# Kitchenkopf-v1_1.net
KiCad netlist of a schematic drawn in EAGLE
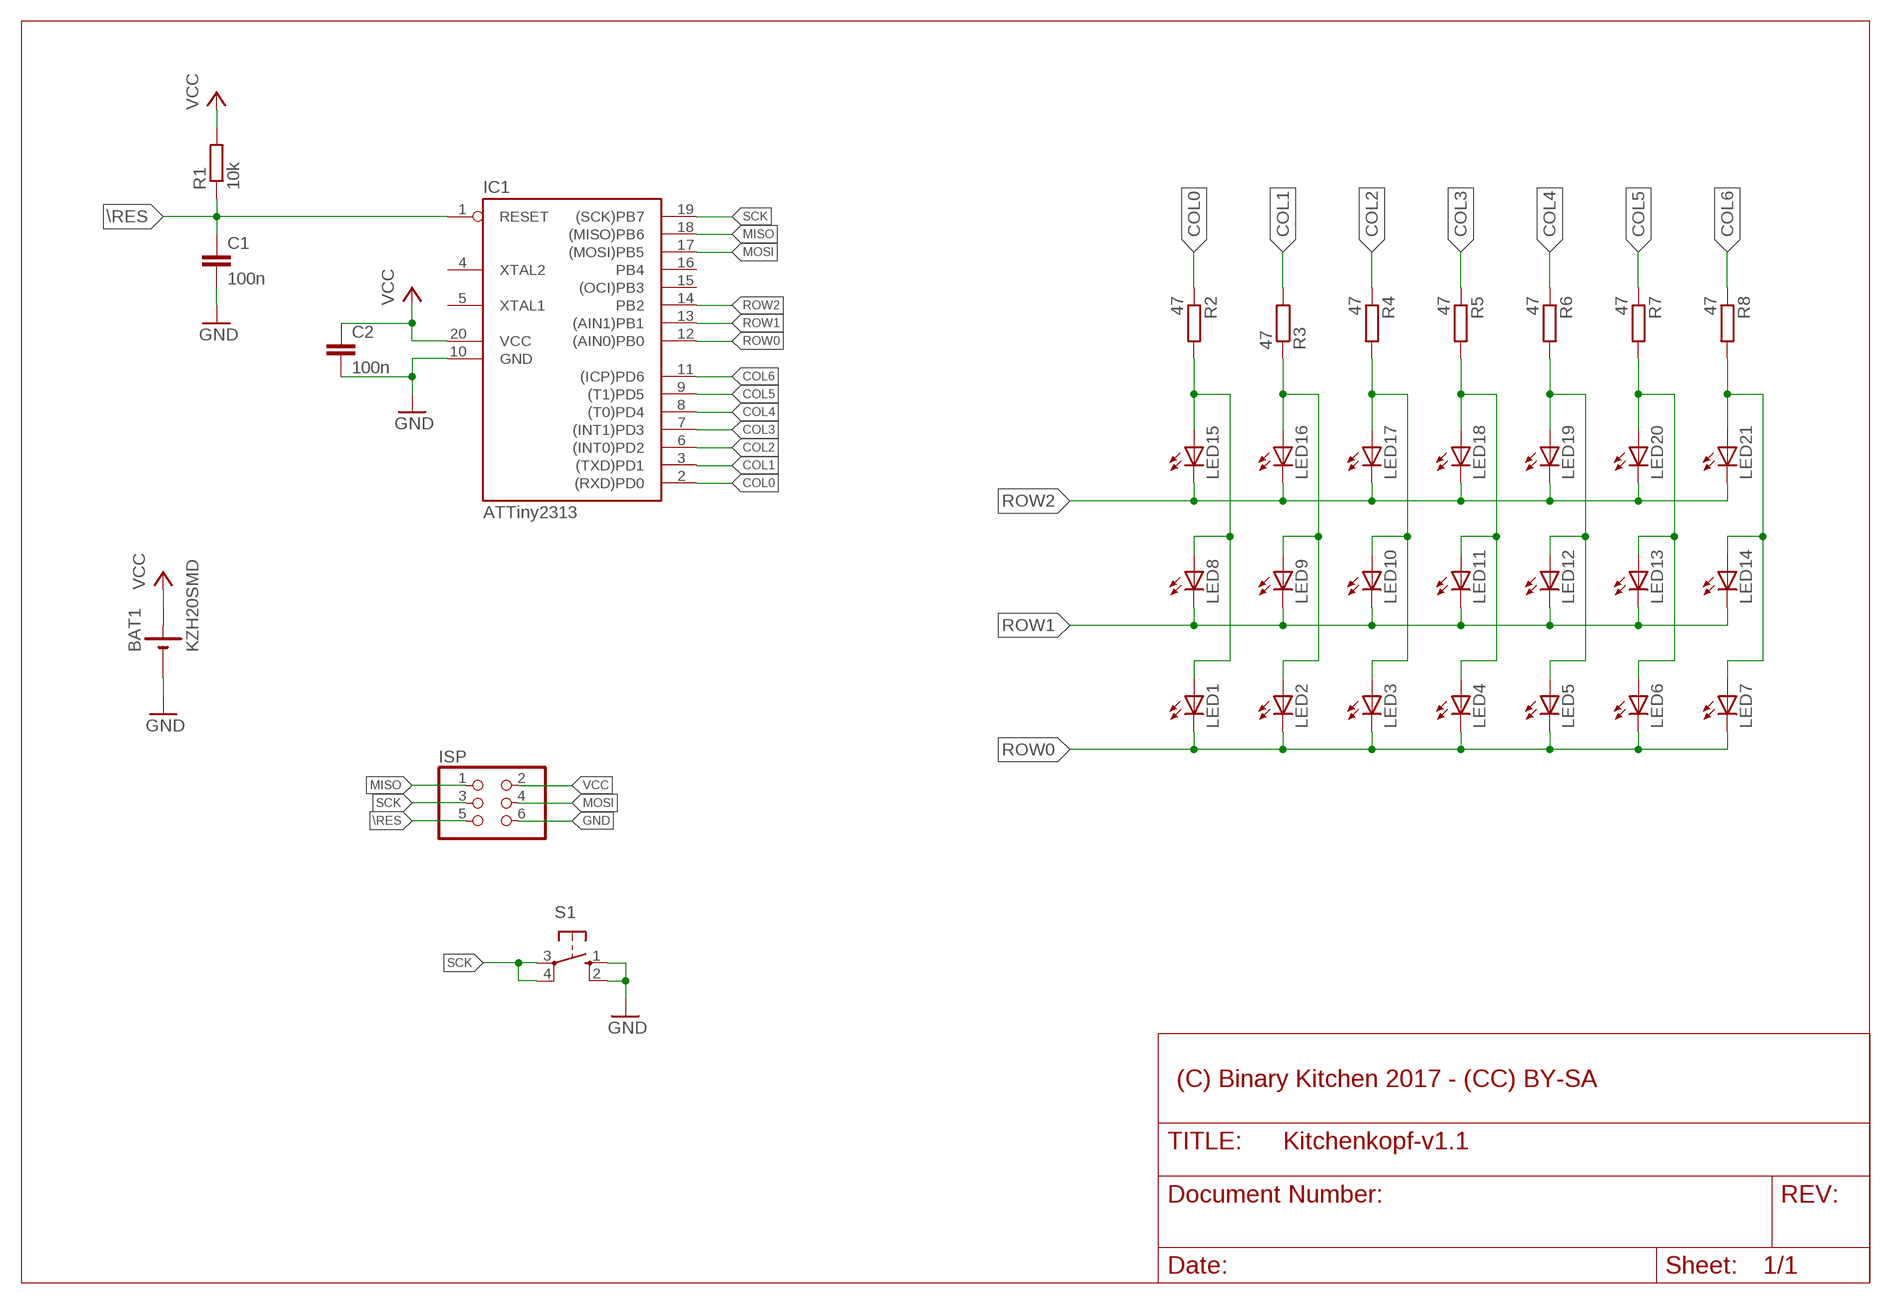
[diagram p0: schematic, sheet 1]

(export (version "E")
  (design (tool "Eeschema 10.0.6"))
  (components
    (comp (ref "BAT1")
      (value "KZH20SMD")
      (footprint "eagle-import:KZH20SMD")
      (libsource (lib "eagle-import") (part "KZH20SMD"))
    )
    (comp (ref "C1")
      (value "100n")
      (footprint "eagle-import:C0805")
      (libsource (lib "eagle-import") (part "C-EUC0805"))
    )
    (comp (ref "C2")
      (value "100n")
      (footprint "eagle-import:C0805")
      (libsource (lib "eagle-import") (part "C-EUC0805"))
    )
    (comp (ref "IC1")
      (value "ATTiny2313")
      (footprint "eagle-import:SO20L")
      (libsource (lib "eagle-import") (part "AT90S2313S"))
    )
    (comp (ref "ISP")
      (value "PINHD-2X03_2.54")
      (footprint "eagle-import:2X03")
      (libsource (lib "eagle-import") (part "PINHD-2X03_2.54"))
    )
    (comp (ref "LED1")
      (value "LEDCHIP-LED0805")
      (footprint "eagle-import:CHIP-LED0805")
      (libsource (lib "eagle-import") (part "LEDCHIP-LED0805"))
    )
    (comp (ref "LED2")
      (value "LEDCHIP-LED0805")
      (footprint "eagle-import:CHIP-LED0805")
      (libsource (lib "eagle-import") (part "LEDCHIP-LED0805"))
    )
    (comp (ref "LED3")
      (value "LEDCHIP-LED0805")
      (footprint "eagle-import:CHIP-LED0805")
      (libsource (lib "eagle-import") (part "LEDCHIP-LED0805"))
    )
    (comp (ref "LED4")
      (value "LEDCHIP-LED0805")
      (footprint "eagle-import:CHIP-LED0805")
      (libsource (lib "eagle-import") (part "LEDCHIP-LED0805"))
    )
    (comp (ref "LED5")
      (value "LEDCHIP-LED0805")
      (footprint "eagle-import:CHIP-LED0805")
      (libsource (lib "eagle-import") (part "LEDCHIP-LED0805"))
    )
    (comp (ref "LED6")
      (value "LEDCHIP-LED0805")
      (footprint "eagle-import:CHIP-LED0805")
      (libsource (lib "eagle-import") (part "LEDCHIP-LED0805"))
    )
    (comp (ref "LED7")
      (value "LEDCHIP-LED0805")
      (footprint "eagle-import:CHIP-LED0805")
      (libsource (lib "eagle-import") (part "LEDCHIP-LED0805"))
    )
    (comp (ref "LED8")
      (value "LEDCHIP-LED0805")
      (footprint "eagle-import:CHIP-LED0805")
      (libsource (lib "eagle-import") (part "LEDCHIP-LED0805"))
    )
    (comp (ref "LED9")
      (value "LEDCHIP-LED0805")
      (footprint "eagle-import:CHIP-LED0805")
      (libsource (lib "eagle-import") (part "LEDCHIP-LED0805"))
    )
    (comp (ref "LED10")
      (value "LEDCHIP-LED0805")
      (footprint "eagle-import:CHIP-LED0805")
      (libsource (lib "eagle-import") (part "LEDCHIP-LED0805"))
    )
    (comp (ref "LED11")
      (value "LEDCHIP-LED0805")
      (footprint "eagle-import:CHIP-LED0805")
      (libsource (lib "eagle-import") (part "LEDCHIP-LED0805"))
    )
    (comp (ref "LED12")
      (value "LEDCHIP-LED0805")
      (footprint "eagle-import:CHIP-LED0805")
      (libsource (lib "eagle-import") (part "LEDCHIP-LED0805"))
    )
    (comp (ref "LED13")
      (value "LEDCHIP-LED0805")
      (footprint "eagle-import:CHIP-LED0805")
      (libsource (lib "eagle-import") (part "LEDCHIP-LED0805"))
    )
    (comp (ref "LED14")
      (value "LEDCHIP-LED0805")
      (footprint "eagle-import:CHIP-LED0805")
      (libsource (lib "eagle-import") (part "LEDCHIP-LED0805"))
    )
    (comp (ref "LED15")
      (value "LEDCHIP-LED0805")
      (footprint "eagle-import:CHIP-LED0805")
      (libsource (lib "eagle-import") (part "LEDCHIP-LED0805"))
    )
    (comp (ref "LED16")
      (value "LEDCHIP-LED0805")
      (footprint "eagle-import:CHIP-LED0805")
      (libsource (lib "eagle-import") (part "LEDCHIP-LED0805"))
    )
    (comp (ref "LED17")
      (value "LEDCHIP-LED0805")
      (footprint "eagle-import:CHIP-LED0805")
      (libsource (lib "eagle-import") (part "LEDCHIP-LED0805"))
    )
    (comp (ref "LED18")
      (value "LEDCHIP-LED0805")
      (footprint "eagle-import:CHIP-LED0805")
      (libsource (lib "eagle-import") (part "LEDCHIP-LED0805"))
    )
    (comp (ref "LED19")
      (value "LEDCHIP-LED0805")
      (footprint "eagle-import:CHIP-LED0805")
      (libsource (lib "eagle-import") (part "LEDCHIP-LED0805"))
    )
    (comp (ref "LED20")
      (value "LEDCHIP-LED0805")
      (footprint "eagle-import:CHIP-LED0805")
      (libsource (lib "eagle-import") (part "LEDCHIP-LED0805"))
    )
    (comp (ref "LED21")
      (value "LEDCHIP-LED0805")
      (footprint "eagle-import:CHIP-LED0805")
      (libsource (lib "eagle-import") (part "LEDCHIP-LED0805"))
    )
    (comp (ref "R1")
      (value "10k")
      (footprint "eagle-import:R0805")
      (libsource (lib "eagle-import") (part "R-EU_R0805"))
    )
    (comp (ref "R2")
      (value "47")
      (footprint "eagle-import:R0805")
      (libsource (lib "eagle-import") (part "R-EU_R0805"))
    )
    (comp (ref "R3")
      (value "47")
      (footprint "eagle-import:R0805")
      (libsource (lib "eagle-import") (part "R-EU_R0805"))
    )
    (comp (ref "R4")
      (value "47")
      (footprint "eagle-import:R0805")
      (libsource (lib "eagle-import") (part "R-EU_R0805"))
    )
    (comp (ref "R5")
      (value "47")
      (footprint "eagle-import:R0805")
      (libsource (lib "eagle-import") (part "R-EU_R0805"))
    )
    (comp (ref "R6")
      (value "47")
      (footprint "eagle-import:R0805")
      (libsource (lib "eagle-import") (part "R-EU_R0805"))
    )
    (comp (ref "R7")
      (value "47")
      (footprint "eagle-import:R0805")
      (libsource (lib "eagle-import") (part "R-EU_R0805"))
    )
    (comp (ref "R8")
      (value "47")
      (footprint "eagle-import:R0805")
      (libsource (lib "eagle-import") (part "R-EU_R0805"))
    )
    (comp (ref "S1")
      (value "10-XX")
      (footprint "eagle-import:B3F-10XX")
      (fields (field (name "MPN") "B3F-1000"))
      (libsource (lib "eagle-import") (part "10-XX"))
    )
  )
  (nets
    (net (code "1") (name "COL0") (class "Default")
      (node (ref "IC1") (pin "2") (pinfunction "(RXD)PD0_2") (pintype "bidirectional"))
      (node (ref "R2") (pin "1") (pinfunction "1_1") (pintype "passive"))
    )
    (net (code "2") (name "COL1") (class "Default")
      (node (ref "IC1") (pin "3") (pinfunction "(TXD)PD1_3") (pintype "bidirectional"))
      (node (ref "R3") (pin "2") (pinfunction "2_2") (pintype "passive"))
    )
    (net (code "3") (name "COL2") (class "Default")
      (node (ref "IC1") (pin "6") (pinfunction "(INT0)PD2_6") (pintype "bidirectional"))
      (node (ref "R4") (pin "1") (pinfunction "1_1") (pintype "passive"))
    )
    (net (code "4") (name "COL3") (class "Default")
      (node (ref "IC1") (pin "7") (pinfunction "(INT1)PD3_7") (pintype "bidirectional"))
      (node (ref "R5") (pin "1") (pinfunction "1_1") (pintype "passive"))
    )
    (net (code "5") (name "COL4") (class "Default")
      (node (ref "IC1") (pin "8") (pinfunction "(T0)PD4_8") (pintype "bidirectional"))
      (node (ref "R6") (pin "1") (pinfunction "1_1") (pintype "passive"))
    )
    (net (code "6") (name "COL5") (class "Default")
      (node (ref "IC1") (pin "9") (pinfunction "(T1)PD5_9") (pintype "bidirectional"))
      (node (ref "R7") (pin "1") (pinfunction "1_1") (pintype "passive"))
    )
    (net (code "7") (name "COL6") (class "Default")
      (node (ref "IC1") (pin "11") (pinfunction "(ICP)PD6_11") (pintype "bidirectional"))
      (node (ref "R8") (pin "1") (pinfunction "1_1") (pintype "passive"))
    )
    (net (code "8") (name "GND") (class "Default")
      (node (ref "BAT1") (pin "NEG") (pinfunction "-_NEG") (pintype "power_in"))
      (node (ref "C1") (pin "2") (pinfunction "2_2") (pintype "passive"))
      (node (ref "C2") (pin "2") (pinfunction "2_2") (pintype "passive"))
      (node (ref "IC1") (pin "10") (pinfunction "GND_10") (pintype "power_in"))
      (node (ref "ISP") (pin "6") (pinfunction "6_6") (pintype "passive"))
      (node (ref "S1") (pin "1") (pinfunction "S_1") (pintype "passive"))
      (node (ref "S1") (pin "2") (pinfunction "S1_2") (pintype "passive"))
    )
    (net (code "9") (name "MISO") (class "Default")
      (node (ref "IC1") (pin "18") (pinfunction "(MISO)PB6_18") (pintype "bidirectional"))
      (node (ref "ISP") (pin "1") (pinfunction "1_1") (pintype "passive"))
    )
    (net (code "10") (name "MOSI") (class "Default")
      (node (ref "IC1") (pin "17") (pinfunction "(MOSI)PB5_17") (pintype "bidirectional"))
      (node (ref "ISP") (pin "4") (pinfunction "4_4") (pintype "passive"))
    )
    (net (code "11") (name "Net-(LED1-PadA)") (class "Default")
      (node (ref "LED1") (pin "A") (pinfunction "A_A") (pintype "passive"))
      (node (ref "LED15") (pin "A") (pinfunction "A_A") (pintype "passive"))
      (node (ref "LED8") (pin "A") (pinfunction "A_A") (pintype "passive"))
      (node (ref "R2") (pin "2") (pinfunction "2_2") (pintype "passive"))
    )
    (net (code "12") (name "Net-(LED10-PadA)") (class "Default")
      (node (ref "LED10") (pin "A") (pinfunction "A_A") (pintype "passive"))
      (node (ref "LED17") (pin "A") (pinfunction "A_A") (pintype "passive"))
      (node (ref "LED3") (pin "A") (pinfunction "A_A") (pintype "passive"))
      (node (ref "R4") (pin "2") (pinfunction "2_2") (pintype "passive"))
    )
    (net (code "13") (name "Net-(LED11-PadA)") (class "Default")
      (node (ref "LED11") (pin "A") (pinfunction "A_A") (pintype "passive"))
      (node (ref "LED18") (pin "A") (pinfunction "A_A") (pintype "passive"))
      (node (ref "LED4") (pin "A") (pinfunction "A_A") (pintype "passive"))
      (node (ref "R5") (pin "2") (pinfunction "2_2") (pintype "passive"))
    )
    (net (code "14") (name "Net-(LED12-PadA)") (class "Default")
      (node (ref "LED12") (pin "A") (pinfunction "A_A") (pintype "passive"))
      (node (ref "LED19") (pin "A") (pinfunction "A_A") (pintype "passive"))
      (node (ref "LED5") (pin "A") (pinfunction "A_A") (pintype "passive"))
      (node (ref "R6") (pin "2") (pinfunction "2_2") (pintype "passive"))
    )
    (net (code "15") (name "Net-(LED13-PadA)") (class "Default")
      (node (ref "LED13") (pin "A") (pinfunction "A_A") (pintype "passive"))
      (node (ref "LED20") (pin "A") (pinfunction "A_A") (pintype "passive"))
      (node (ref "LED6") (pin "A") (pinfunction "A_A") (pintype "passive"))
      (node (ref "R7") (pin "2") (pinfunction "2_2") (pintype "passive"))
    )
    (net (code "16") (name "Net-(LED14-PadA)") (class "Default")
      (node (ref "LED14") (pin "A") (pinfunction "A_A") (pintype "passive"))
      (node (ref "LED21") (pin "A") (pinfunction "A_A") (pintype "passive"))
      (node (ref "LED7") (pin "A") (pinfunction "A_A") (pintype "passive"))
      (node (ref "R8") (pin "2") (pinfunction "2_2") (pintype "passive"))
    )
    (net (code "17") (name "Net-(LED16-PadA)") (class "Default")
      (node (ref "LED16") (pin "A") (pinfunction "A_A") (pintype "passive"))
      (node (ref "LED2") (pin "A") (pinfunction "A_A") (pintype "passive"))
      (node (ref "LED9") (pin "A") (pinfunction "A_A") (pintype "passive"))
      (node (ref "R3") (pin "1") (pinfunction "1_1") (pintype "passive"))
    )
    (net (code "18") (name "ROW0") (class "Default")
      (node (ref "IC1") (pin "12") (pinfunction "(AIN0)PB0_12") (pintype "bidirectional"))
      (node (ref "LED1") (pin "C") (pinfunction "C_C") (pintype "passive"))
      (node (ref "LED2") (pin "C") (pinfunction "C_C") (pintype "passive"))
      (node (ref "LED3") (pin "C") (pinfunction "C_C") (pintype "passive"))
      (node (ref "LED4") (pin "C") (pinfunction "C_C") (pintype "passive"))
      (node (ref "LED5") (pin "C") (pinfunction "C_C") (pintype "passive"))
      (node (ref "LED6") (pin "C") (pinfunction "C_C") (pintype "passive"))
      (node (ref "LED7") (pin "C") (pinfunction "C_C") (pintype "passive"))
    )
    (net (code "19") (name "ROW1") (class "Default")
      (node (ref "IC1") (pin "13") (pinfunction "(AIN1)PB1_13") (pintype "bidirectional"))
      (node (ref "LED10") (pin "C") (pinfunction "C_C") (pintype "passive"))
      (node (ref "LED11") (pin "C") (pinfunction "C_C") (pintype "passive"))
      (node (ref "LED12") (pin "C") (pinfunction "C_C") (pintype "passive"))
      (node (ref "LED13") (pin "C") (pinfunction "C_C") (pintype "passive"))
      (node (ref "LED14") (pin "C") (pinfunction "C_C") (pintype "passive"))
      (node (ref "LED8") (pin "C") (pinfunction "C_C") (pintype "passive"))
      (node (ref "LED9") (pin "C") (pinfunction "C_C") (pintype "passive"))
    )
    (net (code "20") (name "ROW2") (class "Default")
      (node (ref "IC1") (pin "14") (pinfunction "PB2_14") (pintype "bidirectional"))
      (node (ref "LED15") (pin "C") (pinfunction "C_C") (pintype "passive"))
      (node (ref "LED16") (pin "C") (pinfunction "C_C") (pintype "passive"))
      (node (ref "LED17") (pin "C") (pinfunction "C_C") (pintype "passive"))
      (node (ref "LED18") (pin "C") (pinfunction "C_C") (pintype "passive"))
      (node (ref "LED19") (pin "C") (pinfunction "C_C") (pintype "passive"))
      (node (ref "LED20") (pin "C") (pinfunction "C_C") (pintype "passive"))
      (node (ref "LED21") (pin "C") (pinfunction "C_C") (pintype "passive"))
    )
    (net (code "21") (name "SCK") (class "Default")
      (node (ref "IC1") (pin "19") (pinfunction "(SCK)PB7_19") (pintype "bidirectional"))
      (node (ref "ISP") (pin "3") (pinfunction "3_3") (pintype "passive"))
      (node (ref "S1") (pin "3") (pinfunction "P_3") (pintype "passive"))
      (node (ref "S1") (pin "4") (pinfunction "P1_4") (pintype "passive"))
    )
    (net (code "22") (name "VCC") (class "Default")
      (node (ref "BAT1") (pin "POS") (pinfunction "+_POS") (pintype "power_in"))
      (node (ref "C2") (pin "1") (pinfunction "1_1") (pintype "passive"))
      (node (ref "IC1") (pin "20") (pinfunction "VCC_20") (pintype "power_in"))
      (node (ref "ISP") (pin "2") (pinfunction "2_2") (pintype "passive"))
      (node (ref "R1") (pin "2") (pinfunction "2_2") (pintype "passive"))
    )
    (net (code "23") (name "\\RES") (class "Default")
      (node (ref "C1") (pin "1") (pinfunction "1_1") (pintype "passive"))
      (node (ref "IC1") (pin "1") (pinfunction "RESET_1") (pintype "bidirectional"))
      (node (ref "ISP") (pin "5") (pinfunction "5_5") (pintype "passive"))
      (node (ref "R1") (pin "1") (pinfunction "1_1") (pintype "passive"))
    )
    (net (code "24") (name "unconnected-(IC1-(OCI)PB3-Pad15)") (class "Default")
      (node (ref "IC1") (pin "15") (pinfunction "(OCI)PB3_15") (pintype "bidirectional"))
    )
    (net (code "25") (name "unconnected-(IC1-PB4-Pad16)") (class "Default")
      (node (ref "IC1") (pin "16") (pinfunction "PB4_16") (pintype "bidirectional"))
    )
    (net (code "26") (name "unconnected-(IC1-XTAL1-Pad5)") (class "Default")
      (node (ref "IC1") (pin "5") (pinfunction "XTAL1_5") (pintype "bidirectional"))
    )
    (net (code "27") (name "unconnected-(IC1-XTAL2-Pad4)") (class "Default")
      (node (ref "IC1") (pin "4") (pinfunction "XTAL2_4") (pintype "bidirectional"))
    )
  )
)
